# BPM_ver1.net
KiCad netlist of a schematic drawn in EAGLE
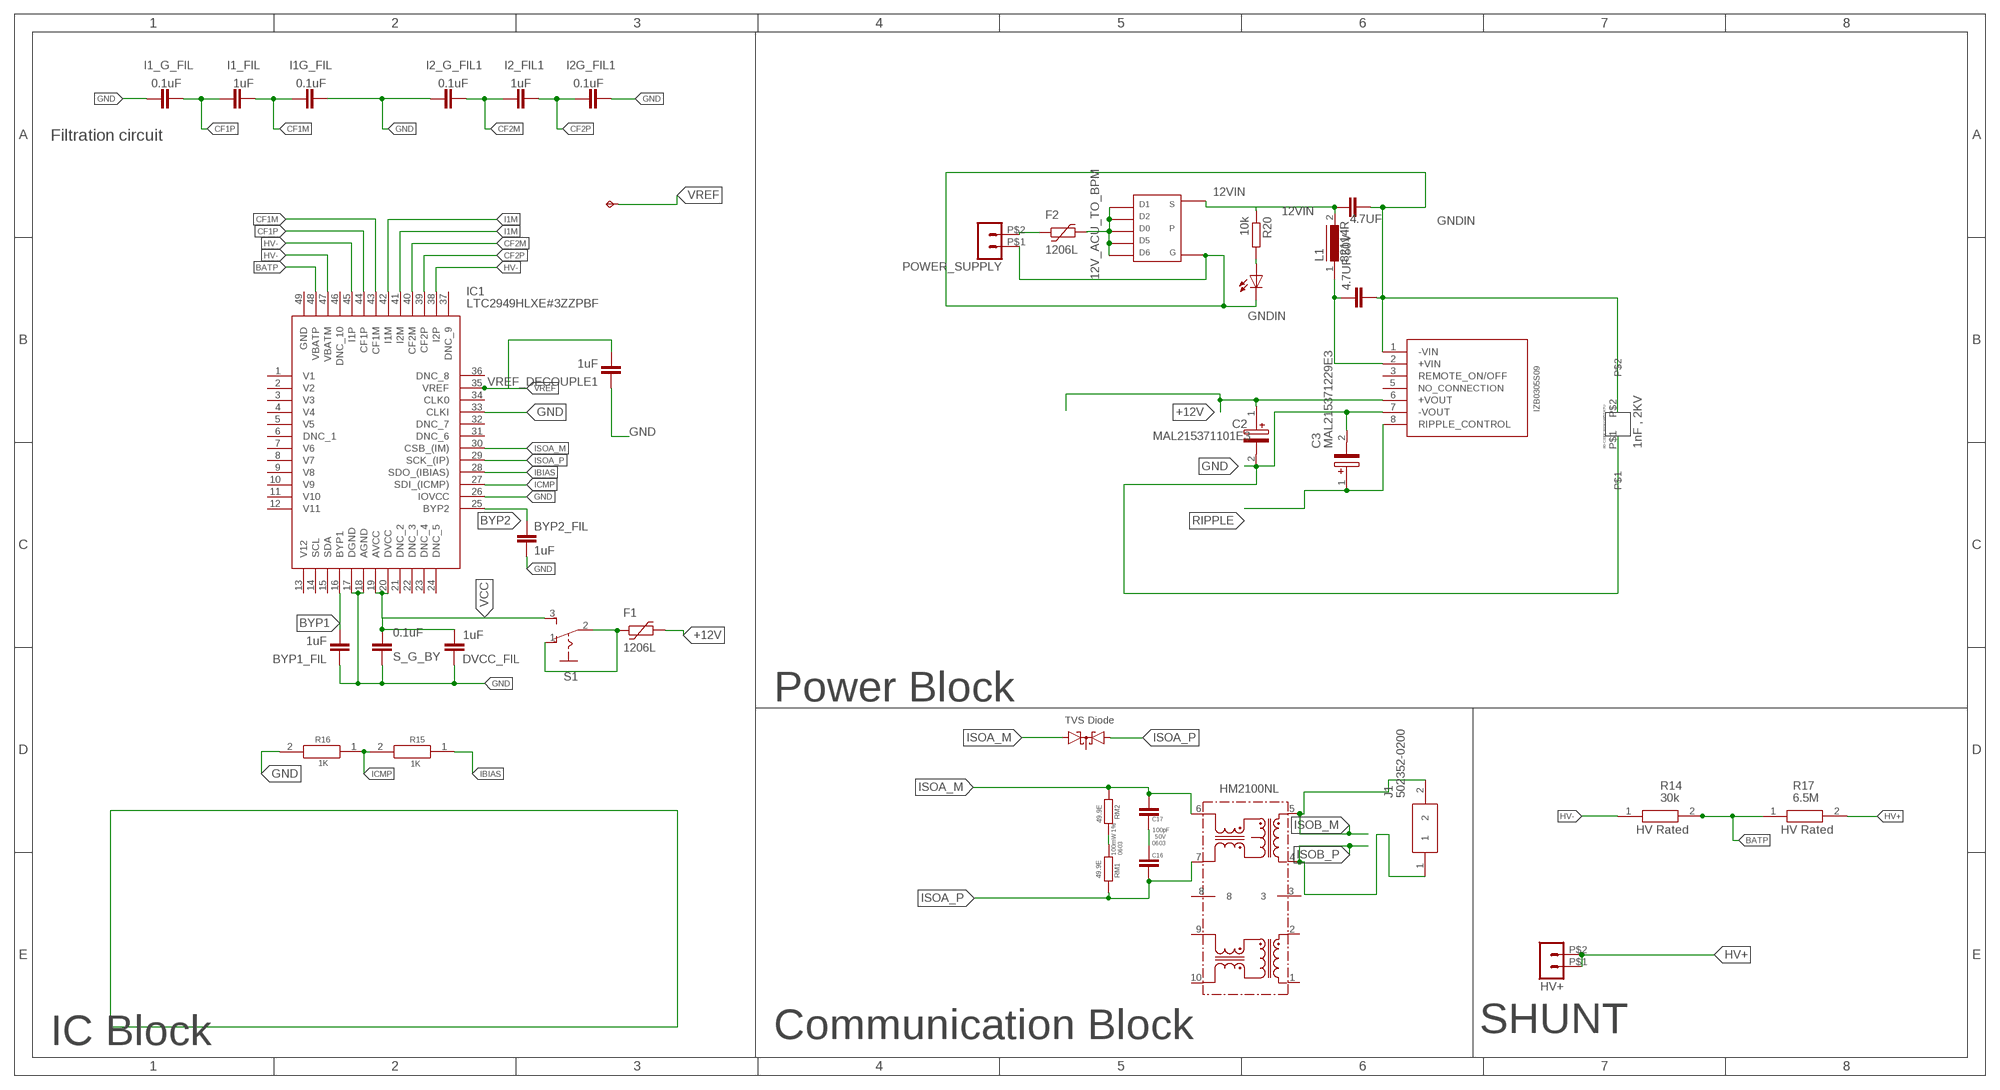
[diagram p0: schematic, sheet 1]

(export (version "E")
  (design (tool "Eeschema 10.0.6"))
  (components
    (comp (ref "4.7UF")
      (value "C-EUC1206")
      (footprint "eagle-import:C1206")
      (libsource (lib "eagle-import") (part "C-EUC1206"))
    )
    (comp (ref "4.7UF,50V")
      (value "C-EUC1206")
      (footprint "eagle-import:C1206")
      (libsource (lib "eagle-import") (part "C-EUC1206"))
    )
    (comp (ref "BYP1_FIL")
      (value "1uF")
      (footprint "eagle-import:C0603")
      (libsource (lib "eagle-import") (part "rcl_334_C-EUC0603"))
    )
    (comp (ref "BYP2_FIL")
      (value "1uF")
      (footprint "eagle-import:C0603")
      (libsource (lib "eagle-import") (part "rcl_334_C-EUC0603"))
    )
    (comp (ref "C2")
      (value "MAL215371101E3")
      (footprint "eagle-import:CAPAE1060X1060N")
      (fields (field (name "MOUSER_PART_NUMBER") "594-MAL215371101E3"))
      (libsource (lib "eagle-import") (part "MAL215371101E3"))
    )
    (comp (ref "C3")
      (value "MAL215371229E3")
      (footprint "eagle-import:CAPAE860X680N")
      (fields (field (name "MOUSER_PART_NUMBER") "594-MAL215371229E3"))
      (libsource (lib "eagle-import") (part "MAL215371229E3"))
    )
    (comp (ref "C15")
      (value "TPPAD1-13")
      (footprint "eagle-import:P1-13")
      (libsource (lib "eagle-import") (part "TPPAD1-13"))
    )
    (comp (ref "C16")
      (value "100pF")
      (footprint "eagle-import:C0603")
      (libsource (lib "eagle-import") (part "resistor_348_C-EUC0603"))
    )
    (comp (ref "C17")
      (value "100pF")
      (footprint "eagle-import:C0603")
      (libsource (lib "eagle-import") (part "resistor_348_C-EUC0603"))
    )
    (comp (ref "DVCC_FIL")
      (value "1uF")
      (footprint "eagle-import:C0603")
      (libsource (lib "eagle-import") (part "rcl_334_C-EUC0603"))
    )
    (comp (ref "F1")
      (value "1206L")
      (footprint "eagle-import:1206L")
      (libsource (lib "eagle-import") (part "1206L"))
    )
    (comp (ref "F2")
      (value "1206L")
      (footprint "eagle-import:1206L")
      (libsource (lib "eagle-import") (part "1206L"))
    )
    (comp (ref "HM2100NL")
      (value "HM2100NL")
      (footprint "eagle-import:HM2100NL")
      (libsource (lib "eagle-import") (part "HM2100NL"))
    )
    (comp (ref "HV+")
      (value "MOLEX2PIN43650-0200")
      (footprint "eagle-import:43650-0200")
      (libsource (lib "eagle-import") (part "MOLEX2PIN43650-0200"))
    )
    (comp (ref "I1G_FIL")
      (value "0.1uF")
      (footprint "eagle-import:C0603")
      (libsource (lib "eagle-import") (part "rcl_334_C-EUC0603"))
    )
    (comp (ref "I1_FIL")
      (value "1uF")
      (footprint "eagle-import:C0603")
      (libsource (lib "eagle-import") (part "rcl_334_C-EUC0603"))
    )
    (comp (ref "I1_G_FIL")
      (value "0.1uF")
      (footprint "eagle-import:C0603")
      (libsource (lib "eagle-import") (part "rcl_334_C-EUC0603"))
    )
    (comp (ref "I2G_FIL1")
      (value "0.1uF")
      (footprint "eagle-import:C0603")
      (libsource (lib "eagle-import") (part "rcl_334_C-EUC0603"))
    )
    (comp (ref "I2_FIL1")
      (value "1uF")
      (footprint "eagle-import:C0603")
      (libsource (lib "eagle-import") (part "rcl_334_C-EUC0603"))
    )
    (comp (ref "I2_G_FIL1")
      (value "0.1uF")
      (footprint "eagle-import:C0603")
      (libsource (lib "eagle-import") (part "rcl_334_C-EUC0603"))
    )
    (comp (ref "IC1")
      (value "LTC2949HLXE#3ZZPBF")
      (footprint "eagle-import:QFP50P900X900X160-49N")
      (fields (field (name "MOUSER_PART_NUMBER") "584-949HLXE#3ZZPBF"))
      (libsource (lib "eagle-import") (part "LTC2949HLXE#3ZZPBF"))
    )
    (comp (ref "IM1")
      (value "TVS")
      (footprint "eagle-import:SOT23")
      (libsource (lib "eagle-import") (part "BAS40-05"))
    )
    (comp (ref "J1")
      (value "502352-0200")
      (footprint "eagle-import:5023520200")
      (fields (field (name "MOUSER_PART_NUMBER") "538-502352-0200"))
      (libsource (lib "eagle-import") (part "502352-0200"))
    )
    (comp (ref "L1")
      (value "82114R")
      (footprint "eagle-import:82114R")
      (libsource (lib "eagle-import") (part "82114R"))
    )
    (comp (ref "POWER_SUPPLY")
      (value "MOLEX2PIN43045-0212")
      (footprint "eagle-import:43045-0212")
      (libsource (lib "eagle-import") (part "MOLEX2PIN43045-0212"))
    )
    (comp (ref "PWR_LED")
      (value "LED-FKIT-1206")
      (footprint "eagle-import:FKIT-LED-1206")
      (libsource (lib "eagle-import") (part "LED-FKIT-1206"))
    )
    (comp (ref "R14")
      (value "30k")
      (footprint "eagle-import:RESC3216X70N")
      (fields (field (name "MANUFACTURER_PART_NUMBER") "HV73V2BTTD6494F"))
      (libsource (lib "eagle-import") (part "HV73V2BTTD6494F"))
    )
    (comp (ref "R15")
      (value "1K")
      (footprint "eagle-import:RESC1608X50N")
      (fields
        (field (name "ARROW_PART_NUMBER") "CRCW06031K00FKEC")
        (field (name "MOUSER_PART_NUMBER") "71-CRCW06031K00FKEC")
      )
      (libsource (lib "eagle-import") (part "CRCW06031K00FKEC"))
    )
    (comp (ref "R16")
      (value "1K")
      (footprint "eagle-import:RESC1608X50N")
      (fields
        (field (name "ARROW_PART_NUMBER") "CRCW06031K00FKEC")
        (field (name "MOUSER_PART_NUMBER") "71-CRCW06031K00FKEC")
      )
      (libsource (lib "eagle-import") (part "CRCW06031K00FKEC"))
    )
    (comp (ref "R17")
      (value "6.5M")
      (footprint "eagle-import:RESC3216X70N")
      (fields (field (name "MANUFACTURER_PART_NUMBER") "HV73V2BTTD6494F"))
      (libsource (lib "eagle-import") (part "HV73V2BTTD6494F"))
    )
    (comp (ref "R20")
      (value "10k")
      (footprint "eagle-import:R0805")
      (libsource (lib "eagle-import") (part "R-EU_R0805"))
    )
    (comp (ref "RM1")
      (value "49.9E")
      (footprint "eagle-import:R0603")
      (libsource (lib "eagle-import") (part "resistor_348_R-EU_R0603"))
    )
    (comp (ref "RM2")
      (value "49.9E")
      (footprint "eagle-import:R0603")
      (libsource (lib "eagle-import") (part "resistor_348_R-EU_R0603"))
    )
    (comp (ref "S1")
      (value "STS121PC04")
      (footprint "eagle-import:STS121PC04")
      (libsource (lib "eagle-import") (part "STS121PC04"))
    )
    (comp (ref "S_G_BY")
      (value "0.1uF")
      (footprint "eagle-import:C0603")
      (libsource (lib "eagle-import") (part "rcl_334_C-EUC0603"))
    )
    (comp (ref "U$1")
      (value "BPM_CONV")
      (footprint "eagle-import:BPM_CONV")
      (libsource (lib "eagle-import") (part "BPM_CONV"))
    )
    (comp (ref "U$2")
      (value "80-C330C102KGR5TATU")
      (footprint "eagle-import:80-C330C102KGR5TATU")
      (libsource (lib "eagle-import") (part "80-C330C102KGR5TATU"))
    )
    (comp (ref "U$10")
      (value "TSOP-6_PMOS")
      (footprint "eagle-import:TSOP-6_PMOS")
      (libsource (lib "eagle-import") (part "TSOP-6_PMOS"))
    )
    (comp (ref "VREF_DECOUPLE1")
      (value "1uF")
      (footprint "eagle-import:C0603")
      (libsource (lib "eagle-import") (part "rcl_334_C-EUC0603"))
    )
  )
  (nets
    (net (code "1") (name "+12V") (class "Default")
      (node (ref "C2") (pin "1") (pinfunction "+_1") (pintype "bidirectional"))
      (node (ref "F1") (pin "P$2") (pinfunction "2_P$2") (pintype "passive"))
      (node (ref "U$1") (pin "6") (pinfunction "+VOUT_6") (pintype "bidirectional"))
    )
    (net (code "2") (name "/12VIN") (class "Default")
      (node (ref "4.7UF") (pin "1") (pinfunction "1_1") (pintype "passive"))
      (node (ref "L1") (pin "2") (pinfunction "2_2") (pintype "passive"))
      (node (ref "R20") (pin "1") (pinfunction "1_1") (pintype "passive"))
      (node (ref "U$10") (pin "S") (pinfunction "S_S") (pintype "bidirectional"))
    )
    (net (code "3") (name "/12V_ACU_TO_BPM") (class "Default")
      (node (ref "F2") (pin "P$2") (pinfunction "2_P$2") (pintype "passive"))
      (node (ref "U$10") (pin "1") (pinfunction "1_1") (pintype "bidirectional"))
      (node (ref "U$10") (pin "2") (pinfunction "2_2") (pintype "bidirectional"))
      (node (ref "U$10") (pin "5") (pinfunction "5_5") (pintype "bidirectional"))
      (node (ref "U$10") (pin "6") (pinfunction "6_6") (pintype "bidirectional"))
      (node (ref "U$10") (pin "D") (pinfunction "D0_D") (pintype "bidirectional"))
    )
    (net (code "4") (name "/GNDIN") (class "Default")
      (node (ref "4.7UF") (pin "2") (pinfunction "2_2") (pintype "passive"))
      (node (ref "4.7UF,50V") (pin "2") (pinfunction "2_2") (pintype "passive"))
      (node (ref "POWER_SUPPLY") (pin "P$1") (pinfunction "1_P$1") (pintype "passive"))
      (node (ref "PWR_LED") (pin "C") (pinfunction "C_C") (pintype "passive"))
      (node (ref "U$1") (pin "1") (pinfunction "-VIN_1") (pintype "bidirectional"))
      (node (ref "U$10") (pin "G") (pinfunction "G_G") (pintype "bidirectional"))
      (node (ref "U$2") (pin "P$2") (pinfunction "P$2_P$2") (pintype "bidirectional"))
    )
    (net (code "5") (name "BATP") (class "Default")
      (node (ref "IC1") (pin "48") (pinfunction "VBATP_48") (pintype "bidirectional"))
      (node (ref "R14") (pin "2") (pinfunction "2_2") (pintype "bidirectional"))
      (node (ref "R17") (pin "1") (pinfunction "1_1") (pintype "bidirectional"))
    )
    (net (code "6") (name "BYP1") (class "Default")
      (node (ref "BYP1_FIL") (pin "2") (pinfunction "2_2") (pintype "passive"))
      (node (ref "IC1") (pin "16") (pinfunction "BYP1_16") (pintype "bidirectional"))
    )
    (net (code "7") (name "BYP2") (class "Default")
      (node (ref "BYP2_FIL") (pin "1") (pinfunction "1_1") (pintype "passive"))
      (node (ref "IC1") (pin "25") (pinfunction "BYP2_25") (pintype "bidirectional"))
    )
    (net (code "8") (name "CF1M") (class "Default")
      (node (ref "I1G_FIL") (pin "1") (pinfunction "1_1") (pintype "passive"))
      (node (ref "I1_FIL") (pin "1") (pinfunction "1_1") (pintype "passive"))
      (node (ref "IC1") (pin "43") (pinfunction "CF1M_43") (pintype "bidirectional"))
    )
    (net (code "9") (name "CF1P") (class "Default")
      (node (ref "I1_FIL") (pin "2") (pinfunction "2_2") (pintype "passive"))
      (node (ref "I1_G_FIL") (pin "2") (pinfunction "2_2") (pintype "passive"))
      (node (ref "IC1") (pin "44") (pinfunction "CF1P_44") (pintype "bidirectional"))
    )
    (net (code "10") (name "CF2M") (class "Default")
      (node (ref "I2_FIL1") (pin "2") (pinfunction "2_2") (pintype "passive"))
      (node (ref "I2_G_FIL1") (pin "1") (pinfunction "1_1") (pintype "passive"))
      (node (ref "IC1") (pin "40") (pinfunction "CF2M_40") (pintype "bidirectional"))
    )
    (net (code "11") (name "CF2P") (class "Default")
      (node (ref "I2G_FIL1") (pin "1") (pinfunction "1_1") (pintype "passive"))
      (node (ref "I2_FIL1") (pin "1") (pinfunction "1_1") (pintype "passive"))
      (node (ref "IC1") (pin "39") (pinfunction "CF2P_39") (pintype "bidirectional"))
    )
    (net (code "12") (name "GND") (class "Default")
      (node (ref "BYP1_FIL") (pin "1") (pinfunction "1_1") (pintype "passive"))
      (node (ref "BYP2_FIL") (pin "2") (pinfunction "2_2") (pintype "passive"))
      (node (ref "C2") (pin "2") (pinfunction "-_2") (pintype "bidirectional"))
      (node (ref "C3") (pin "2") (pinfunction "-_2") (pintype "bidirectional"))
      (node (ref "DVCC_FIL") (pin "1") (pinfunction "1_1") (pintype "passive"))
      (node (ref "I1G_FIL") (pin "2") (pinfunction "2_2") (pintype "passive"))
      (node (ref "I1_G_FIL") (pin "1") (pinfunction "1_1") (pintype "passive"))
      (node (ref "I2G_FIL1") (pin "2") (pinfunction "2_2") (pintype "passive"))
      (node (ref "I2_G_FIL1") (pin "2") (pinfunction "2_2") (pintype "passive"))
      (node (ref "IC1") (pin "17") (pinfunction "DGND_17") (pintype "bidirectional"))
      (node (ref "IC1") (pin "18") (pinfunction "AGND_18") (pintype "bidirectional"))
      (node (ref "IC1") (pin "26") (pinfunction "IOVCC_26") (pintype "bidirectional"))
      (node (ref "IC1") (pin "33") (pinfunction "CLKI_33") (pintype "bidirectional"))
      (node (ref "R16") (pin "2") (pinfunction "2_2") (pintype "bidirectional"))
      (node (ref "S_G_BY") (pin "1") (pinfunction "1_1") (pintype "passive"))
      (node (ref "U$1") (pin "7") (pinfunction "-VOUT_7") (pintype "bidirectional"))
      (node (ref "U$2") (pin "P$1") (pinfunction "P$1_P$1") (pintype "bidirectional"))
      (node (ref "VREF_DECOUPLE1") (pin "1") (pinfunction "1_1") (pintype "passive"))
    )
    (net (code "13") (name "HV+") (class "Default")
      (node (ref "HV+") (pin "P$1") (pinfunction "1_P$1") (pintype "passive"))
      (node (ref "HV+") (pin "P$2") (pinfunction "2_P$2") (pintype "passive"))
      (node (ref "R17") (pin "2") (pinfunction "2_2") (pintype "bidirectional"))
    )
    (net (code "14") (name "HV-") (class "Default")
      (node (ref "IC1") (pin "38") (pinfunction "I2P_38") (pintype "bidirectional"))
      (node (ref "IC1") (pin "45") (pinfunction "I1P_45") (pintype "bidirectional"))
      (node (ref "IC1") (pin "47") (pinfunction "VBATM_47") (pintype "bidirectional"))
      (node (ref "R14") (pin "1") (pinfunction "1_1") (pintype "bidirectional"))
    )
    (net (code "15") (name "I1M") (class "Default")
      (node (ref "IC1") (pin "41") (pinfunction "I2M_41") (pintype "bidirectional"))
      (node (ref "IC1") (pin "42") (pinfunction "I1M_42") (pintype "bidirectional"))
    )
    (net (code "16") (name "IBIAS") (class "Default")
      (node (ref "IC1") (pin "28") (pinfunction "SDO_(IBIAS)_28") (pintype "bidirectional"))
      (node (ref "R15") (pin "1") (pinfunction "1_1") (pintype "bidirectional"))
    )
    (net (code "17") (name "ICMP") (class "Default")
      (node (ref "IC1") (pin "27") (pinfunction "SDI_(ICMP)_27") (pintype "bidirectional"))
      (node (ref "R15") (pin "2") (pinfunction "2_2") (pintype "bidirectional"))
      (node (ref "R16") (pin "1") (pinfunction "1_1") (pintype "bidirectional"))
    )
    (net (code "18") (name "ISOA_M") (class "Default")
      (node (ref "C17") (pin "2") (pinfunction "2_2") (pintype "passive"))
      (node (ref "HM2100NL") (pin "6") (pinfunction "6_6") (pintype "passive"))
      (node (ref "IC1") (pin "30") (pinfunction "CSB_(IM)_30") (pintype "bidirectional"))
      (node (ref "IM1") (pin "2") (pinfunction "A2_2") (pintype "passive"))
      (node (ref "RM2") (pin "1") (pinfunction "1_1") (pintype "passive"))
    )
    (net (code "19") (name "ISOA_P") (class "Default")
      (node (ref "C16") (pin "1") (pinfunction "1_1") (pintype "passive"))
      (node (ref "HM2100NL") (pin "7") (pinfunction "7_7") (pintype "passive"))
      (node (ref "IC1") (pin "29") (pinfunction "SCK_(IP)_29") (pintype "bidirectional"))
      (node (ref "IM1") (pin "1") (pinfunction "A1_1") (pintype "passive"))
      (node (ref "RM1") (pin "2") (pinfunction "2_2") (pintype "passive"))
    )
    (net (code "20") (name "ISOB_M") (class "Default")
      (node (ref "HM2100NL") (pin "5") (pinfunction "5_5") (pintype "passive"))
      (node (ref "J1") (pin "2") (pinfunction "2_2") (pintype "bidirectional"))
    )
    (net (code "21") (name "ISOB_P") (class "Default")
      (node (ref "HM2100NL") (pin "4") (pinfunction "4_4") (pintype "passive"))
      (node (ref "J1") (pin "1") (pinfunction "1_1") (pintype "bidirectional"))
    )
    (net (code "22") (name "Net-(C16-Pad2)") (class "Default")
      (node (ref "C16") (pin "2") (pinfunction "2_2") (pintype "passive"))
      (node (ref "C17") (pin "1") (pinfunction "1_1") (pintype "passive"))
    )
    (net (code "23") (name "Net-(F1-1)") (class "Default")
      (node (ref "F1") (pin "P$1") (pinfunction "1_P$1") (pintype "passive"))
      (node (ref "S1") (pin "1") (pinfunction "O_1") (pintype "passive"))
      (node (ref "S1") (pin "2") (pinfunction "P_2") (pintype "passive"))
    )
    (net (code "24") (name "Net-(F2-1)") (class "Default")
      (node (ref "F2") (pin "P$1") (pinfunction "1_P$1") (pintype "passive"))
      (node (ref "POWER_SUPPLY") (pin "P$2") (pinfunction "2_P$2") (pintype "passive"))
    )
    (net (code "25") (name "Net-(PWR_LED-PadA)") (class "Default")
      (node (ref "PWR_LED") (pin "A") (pinfunction "A_A") (pintype "passive"))
      (node (ref "R20") (pin "2") (pinfunction "2_2") (pintype "passive"))
    )
    (net (code "26") (name "Net-(RM1-Pad1)") (class "Default")
      (node (ref "RM1") (pin "1") (pinfunction "1_1") (pintype "passive"))
      (node (ref "RM2") (pin "2") (pinfunction "2_2") (pintype "passive"))
    )
    (net (code "27") (name "Net-(U$1-+VIN)") (class "Default")
      (node (ref "4.7UF,50V") (pin "1") (pinfunction "1_1") (pintype "passive"))
      (node (ref "L1") (pin "1") (pinfunction "1_1") (pintype "passive"))
      (node (ref "U$1") (pin "2") (pinfunction "+VIN_2") (pintype "bidirectional"))
    )
    (net (code "28") (name "RIPPLE") (class "Default")
      (node (ref "C3") (pin "1") (pinfunction "+_1") (pintype "bidirectional"))
      (node (ref "U$1") (pin "8") (pinfunction "RIPPLE_CONTROL_8") (pintype "bidirectional"))
    )
    (net (code "29") (name "VCC") (class "Default")
      (node (ref "DVCC_FIL") (pin "2") (pinfunction "2_2") (pintype "passive"))
      (node (ref "IC1") (pin "19") (pinfunction "AVCC_19") (pintype "bidirectional"))
      (node (ref "IC1") (pin "20") (pinfunction "DVCC_20") (pintype "bidirectional"))
      (node (ref "S1") (pin "3") (pinfunction "S_3") (pintype "passive"))
      (node (ref "S_G_BY") (pin "2") (pinfunction "2_2") (pintype "passive"))
    )
    (net (code "30") (name "VREF") (class "Default")
      (node (ref "C15") (pin "TP") (pinfunction "TP_TP") (pintype "input"))
      (node (ref "IC1") (pin "35") (pinfunction "VREF_35") (pintype "bidirectional"))
      (node (ref "VREF_DECOUPLE1") (pin "2") (pinfunction "2_2") (pintype "passive"))
    )
    (net (code "31") (name "unconnected-(HM2100NL-Pad1)") (class "Default")
      (node (ref "HM2100NL") (pin "1") (pinfunction "1_1") (pintype "passive"))
    )
    (net (code "32") (name "unconnected-(HM2100NL-Pad2)") (class "Default")
      (node (ref "HM2100NL") (pin "2") (pinfunction "2_2") (pintype "passive"))
    )
    (net (code "33") (name "unconnected-(HM2100NL-Pad3)") (class "Default")
      (node (ref "HM2100NL") (pin "3") (pinfunction "3_3") (pintype "bidirectional"))
    )
    (net (code "34") (name "unconnected-(HM2100NL-Pad8)") (class "Default")
      (node (ref "HM2100NL") (pin "8") (pinfunction "8_8") (pintype "bidirectional"))
    )
    (net (code "35") (name "unconnected-(HM2100NL-Pad9)") (class "Default")
      (node (ref "HM2100NL") (pin "9") (pinfunction "9_9") (pintype "passive"))
    )
    (net (code "36") (name "unconnected-(HM2100NL-Pad10)") (class "Default")
      (node (ref "HM2100NL") (pin "10") (pinfunction "10_10") (pintype "passive"))
    )
    (net (code "37") (name "unconnected-(IC1-CLK0-Pad34)") (class "Default")
      (node (ref "IC1") (pin "34") (pinfunction "CLK0_34") (pintype "bidirectional"))
    )
    (net (code "38") (name "unconnected-(IC1-DNC_1-Pad6)") (class "Default")
      (node (ref "IC1") (pin "6") (pinfunction "DNC_1_6") (pintype "bidirectional"))
    )
    (net (code "39") (name "unconnected-(IC1-DNC_2-Pad21)") (class "Default")
      (node (ref "IC1") (pin "21") (pinfunction "DNC_2_21") (pintype "bidirectional"))
    )
    (net (code "40") (name "unconnected-(IC1-DNC_3-Pad22)") (class "Default")
      (node (ref "IC1") (pin "22") (pinfunction "DNC_3_22") (pintype "bidirectional"))
    )
    (net (code "41") (name "unconnected-(IC1-DNC_4-Pad23)") (class "Default")
      (node (ref "IC1") (pin "23") (pinfunction "DNC_4_23") (pintype "bidirectional"))
    )
    (net (code "42") (name "unconnected-(IC1-DNC_5-Pad24)") (class "Default")
      (node (ref "IC1") (pin "24") (pinfunction "DNC_5_24") (pintype "bidirectional"))
    )
    (net (code "43") (name "unconnected-(IC1-DNC_6-Pad31)") (class "Default")
      (node (ref "IC1") (pin "31") (pinfunction "DNC_6_31") (pintype "bidirectional"))
    )
    (net (code "44") (name "unconnected-(IC1-DNC_7-Pad32)") (class "Default")
      (node (ref "IC1") (pin "32") (pinfunction "DNC_7_32") (pintype "bidirectional"))
    )
    (net (code "45") (name "unconnected-(IC1-DNC_8-Pad36)") (class "Default")
      (node (ref "IC1") (pin "36") (pinfunction "DNC_8_36") (pintype "bidirectional"))
    )
    (net (code "46") (name "unconnected-(IC1-DNC_9-Pad37)") (class "Default")
      (node (ref "IC1") (pin "37") (pinfunction "DNC_9_37") (pintype "bidirectional"))
    )
    (net (code "47") (name "unconnected-(IC1-DNC_10-Pad46)") (class "Default")
      (node (ref "IC1") (pin "46") (pinfunction "DNC_10_46") (pintype "bidirectional"))
    )
    (net (code "48") (name "unconnected-(IC1-GND-Pad49)") (class "Default")
      (node (ref "IC1") (pin "49") (pinfunction "GND_49") (pintype "bidirectional"))
    )
    (net (code "49") (name "unconnected-(IC1-SCL-Pad14)") (class "Default")
      (node (ref "IC1") (pin "14") (pinfunction "SCL_14") (pintype "bidirectional"))
    )
    (net (code "50") (name "unconnected-(IC1-SDA-Pad15)") (class "Default")
      (node (ref "IC1") (pin "15") (pinfunction "SDA_15") (pintype "bidirectional"))
    )
    (net (code "51") (name "unconnected-(IC1-V1-Pad1)") (class "Default")
      (node (ref "IC1") (pin "1") (pinfunction "V1_1") (pintype "bidirectional"))
    )
    (net (code "52") (name "unconnected-(IC1-V2-Pad2)") (class "Default")
      (node (ref "IC1") (pin "2") (pinfunction "V2_2") (pintype "bidirectional"))
    )
    (net (code "53") (name "unconnected-(IC1-V3-Pad3)") (class "Default")
      (node (ref "IC1") (pin "3") (pinfunction "V3_3") (pintype "bidirectional"))
    )
    (net (code "54") (name "unconnected-(IC1-V4-Pad4)") (class "Default")
      (node (ref "IC1") (pin "4") (pinfunction "V4_4") (pintype "bidirectional"))
    )
    (net (code "55") (name "unconnected-(IC1-V5-Pad5)") (class "Default")
      (node (ref "IC1") (pin "5") (pinfunction "V5_5") (pintype "bidirectional"))
    )
    (net (code "56") (name "unconnected-(IC1-V6-Pad7)") (class "Default")
      (node (ref "IC1") (pin "7") (pinfunction "V6_7") (pintype "bidirectional"))
    )
    (net (code "57") (name "unconnected-(IC1-V7-Pad8)") (class "Default")
      (node (ref "IC1") (pin "8") (pinfunction "V7_8") (pintype "bidirectional"))
    )
    (net (code "58") (name "unconnected-(IC1-V8-Pad9)") (class "Default")
      (node (ref "IC1") (pin "9") (pinfunction "V8_9") (pintype "bidirectional"))
    )
    (net (code "59") (name "unconnected-(IC1-V9-Pad10)") (class "Default")
      (node (ref "IC1") (pin "10") (pinfunction "V9_10") (pintype "bidirectional"))
    )
    (net (code "60") (name "unconnected-(IC1-V10-Pad11)") (class "Default")
      (node (ref "IC1") (pin "11") (pinfunction "V10_11") (pintype "bidirectional"))
    )
    (net (code "61") (name "unconnected-(IC1-V11-Pad12)") (class "Default")
      (node (ref "IC1") (pin "12") (pinfunction "V11_12") (pintype "bidirectional"))
    )
    (net (code "62") (name "unconnected-(IC1-V12-Pad13)") (class "Default")
      (node (ref "IC1") (pin "13") (pinfunction "V12_13") (pintype "bidirectional"))
    )
    (net (code "63") (name "unconnected-(IM1-C-Pad3)") (class "Default")
      (node (ref "IM1") (pin "3") (pinfunction "C_3") (pintype "passive"))
    )
    (net (code "64") (name "unconnected-(U$1-REMOTE_ON{slash}OFF-Pad3)") (class "Default")
      (node (ref "U$1") (pin "3") (pinfunction "REMOTE_ON/OFF_3") (pintype "bidirectional"))
    )
  )
)
